# explorer.net
KiCad netlist of a schematic drawn in EAGLE
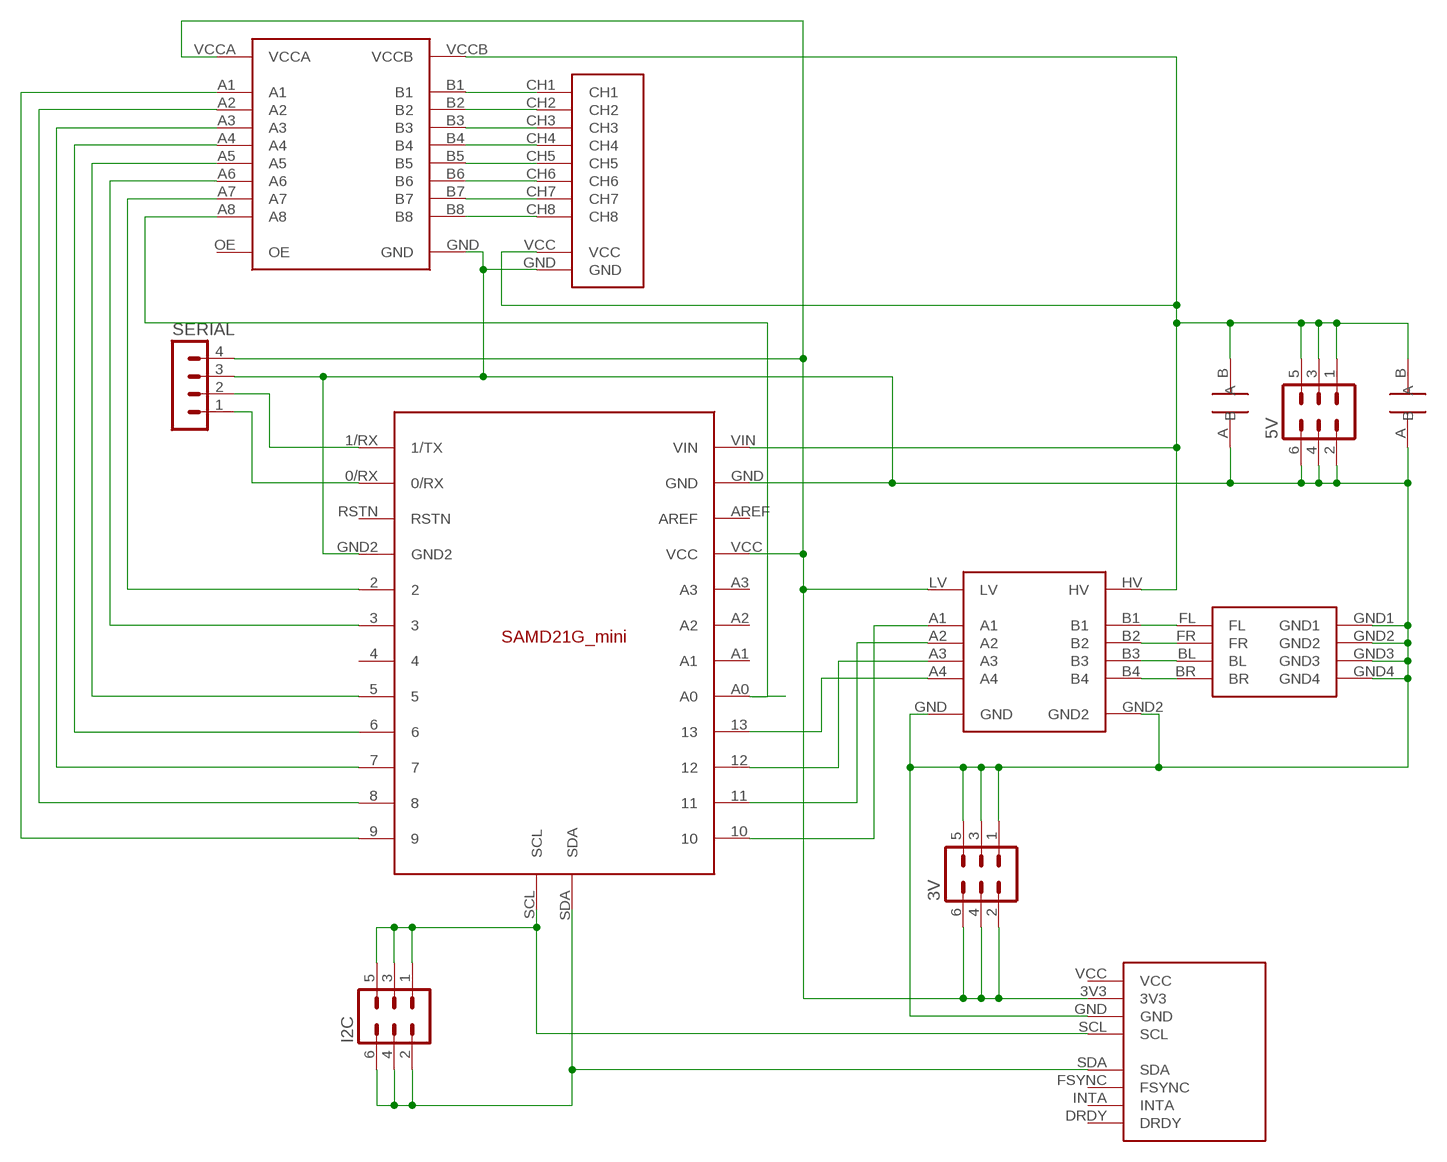
[diagram p0: schematic, sheet 1]

(export (version "E")
  (design (tool "Eeschema 10.0.6"))
  (components
    (comp (ref "3V")
      (value "MA03-2")
      (footprint "eagle-import:MA03-2")
      (libsource (lib "eagle-import") (part "MA03-2"))
    )
    (comp (ref "5V")
      (value "MA03-2")
      (footprint "eagle-import:MA03-2")
      (libsource (lib "eagle-import") (part "MA03-2"))
    )
    (comp (ref "I2C")
      (value "MA03-2")
      (footprint "eagle-import:MA03-2")
      (libsource (lib "eagle-import") (part "MA03-2"))
    )
    (comp (ref "SERIAL")
      (value "MA04-1")
      (footprint "eagle-import:MA04-1")
      (libsource (lib "eagle-import") (part "MA04-1"))
    )
    (comp (ref "U$1")
      (value "MOTOR_HEADER")
      (footprint "eagle-import:MOTOR_HEADER")
      (libsource (lib "eagle-import") (part "MOTOR_HEADER"))
    )
    (comp (ref "U$2")
      (value "CAP")
      (footprint "eagle-import:CAP")
      (libsource (lib "eagle-import") (part "CAP"))
    )
    (comp (ref "U$3")
      (value "SAMD21G_MINI")
      (footprint "eagle-import:SAMD21G-MINI")
      (libsource (lib "eagle-import") (part "SAMD21G_MINI"))
    )
    (comp (ref "U$4")
      (value "LEVELSHIFT_8CH")
      (footprint "eagle-import:LEVELSHIFT_8CH")
      (libsource (lib "eagle-import") (part "LEVELSHIFT_8CH"))
    )
    (comp (ref "U$5")
      (value "LEVELSHIFT_4CH")
      (footprint "eagle-import:LEVELSHIFT_4CH")
      (libsource (lib "eagle-import") (part "LEVELSHIFT_4CH"))
    )
    (comp (ref "U$6")
      (value "RADIO_8CH")
      (footprint "eagle-import:RADIO_8CH")
      (libsource (lib "eagle-import") (part "RADIO_8CH"))
    )
    (comp (ref "U$7")
      (value "CAP")
      (footprint "eagle-import:CAP")
      (libsource (lib "eagle-import") (part "CAP"))
    )
    (comp (ref "U$8")
      (value "GY-86")
      (footprint "eagle-import:GY-86")
      (libsource (lib "eagle-import") (part "GY-86"))
    )
  )
  (nets
    (net (code "1") (name "Net-(3V-Pad1)") (class "Default")
      (node (ref "3V") (pin "1") (pinfunction "1_1") (pintype "passive"))
      (node (ref "3V") (pin "3") (pinfunction "3_3") (pintype "passive"))
      (node (ref "3V") (pin "5") (pinfunction "5_5") (pintype "passive"))
      (node (ref "5V") (pin "2") (pinfunction "2_2") (pintype "passive"))
      (node (ref "5V") (pin "4") (pinfunction "4_4") (pintype "passive"))
      (node (ref "5V") (pin "6") (pinfunction "6_6") (pintype "passive"))
      (node (ref "SERIAL") (pin "3") (pinfunction "3_3") (pintype "passive"))
      (node (ref "U$1") (pin "GND1") (pinfunction "GND1_GND1") (pintype "bidirectional"))
      (node (ref "U$1") (pin "GND2") (pinfunction "GND2_GND2") (pintype "bidirectional"))
      (node (ref "U$1") (pin "GND3") (pinfunction "GND3_GND3") (pintype "bidirectional"))
      (node (ref "U$1") (pin "GND4") (pinfunction "GND4_GND4") (pintype "bidirectional"))
      (node (ref "U$2") (pin "A") (pinfunction "A_A") (pintype "bidirectional"))
      (node (ref "U$3") (pin "GND") (pinfunction "GND_GND") (pintype "bidirectional"))
      (node (ref "U$3") (pin "GND2") (pinfunction "GND2_GND2") (pintype "bidirectional"))
      (node (ref "U$4") (pin "GND") (pinfunction "GND_GND") (pintype "bidirectional"))
      (node (ref "U$5") (pin "GND") (pinfunction "GND_GND") (pintype "bidirectional"))
      (node (ref "U$5") (pin "GND2") (pinfunction "GND2_GND2") (pintype "bidirectional"))
      (node (ref "U$6") (pin "GND") (pinfunction "GND_GND") (pintype "bidirectional"))
      (node (ref "U$7") (pin "A") (pinfunction "A_A") (pintype "bidirectional"))
      (node (ref "U$8") (pin "GND") (pinfunction "GND_GND") (pintype "bidirectional"))
    )
    (net (code "2") (name "Net-(3V-Pad2)") (class "Default")
      (node (ref "3V") (pin "2") (pinfunction "2_2") (pintype "passive"))
      (node (ref "3V") (pin "4") (pinfunction "4_4") (pintype "passive"))
      (node (ref "3V") (pin "6") (pinfunction "6_6") (pintype "passive"))
      (node (ref "SERIAL") (pin "4") (pinfunction "4_4") (pintype "passive"))
      (node (ref "U$3") (pin "VCC") (pinfunction "VCC_VCC") (pintype "bidirectional"))
      (node (ref "U$4") (pin "VCCA") (pinfunction "VCCA_VCCA") (pintype "bidirectional"))
      (node (ref "U$5") (pin "LV") (pinfunction "LV_LV") (pintype "bidirectional"))
      (node (ref "U$8") (pin "3V3") (pinfunction "3V3_3V3") (pintype "bidirectional"))
    )
    (net (code "3") (name "Net-(5V-Pad1)") (class "Default")
      (node (ref "5V") (pin "1") (pinfunction "1_1") (pintype "passive"))
      (node (ref "5V") (pin "3") (pinfunction "3_3") (pintype "passive"))
      (node (ref "5V") (pin "5") (pinfunction "5_5") (pintype "passive"))
      (node (ref "U$2") (pin "B") (pinfunction "B_B") (pintype "bidirectional"))
      (node (ref "U$3") (pin "VIN") (pinfunction "VIN_VIN") (pintype "bidirectional"))
      (node (ref "U$4") (pin "VCCB") (pinfunction "VCCB_VCCB") (pintype "bidirectional"))
      (node (ref "U$5") (pin "HV") (pinfunction "HV_HV") (pintype "bidirectional"))
      (node (ref "U$6") (pin "VCC") (pinfunction "VCC_VCC") (pintype "bidirectional"))
      (node (ref "U$7") (pin "B") (pinfunction "B_B") (pintype "bidirectional"))
    )
    (net (code "4") (name "Net-(I2C-Pad1)") (class "Default")
      (node (ref "I2C") (pin "1") (pinfunction "1_1") (pintype "passive"))
      (node (ref "I2C") (pin "3") (pinfunction "3_3") (pintype "passive"))
      (node (ref "I2C") (pin "5") (pinfunction "5_5") (pintype "passive"))
      (node (ref "U$3") (pin "SCL") (pinfunction "SCL_SCL") (pintype "bidirectional"))
      (node (ref "U$8") (pin "SCL") (pinfunction "SCL_SCL") (pintype "bidirectional"))
    )
    (net (code "5") (name "Net-(I2C-Pad2)") (class "Default")
      (node (ref "I2C") (pin "2") (pinfunction "2_2") (pintype "passive"))
      (node (ref "I2C") (pin "4") (pinfunction "4_4") (pintype "passive"))
      (node (ref "I2C") (pin "6") (pinfunction "6_6") (pintype "passive"))
      (node (ref "U$3") (pin "SDA") (pinfunction "SDA_SDA") (pintype "bidirectional"))
      (node (ref "U$8") (pin "SDA") (pinfunction "SDA_SDA") (pintype "bidirectional"))
    )
    (net (code "6") (name "Net-(SERIAL-Pad1)") (class "Default")
      (node (ref "SERIAL") (pin "1") (pinfunction "1_1") (pintype "passive"))
      (node (ref "U$3") (pin "0/RX") (pinfunction "0/RX_0/RX") (pintype "bidirectional"))
    )
    (net (code "7") (name "Net-(U$1-PadBL)") (class "Default")
      (node (ref "U$1") (pin "BL") (pinfunction "BL_BL") (pintype "bidirectional"))
      (node (ref "U$5") (pin "B3") (pinfunction "B3_B3") (pintype "bidirectional"))
    )
    (net (code "8") (name "Net-(U$1-PadBR)") (class "Default")
      (node (ref "U$1") (pin "BR") (pinfunction "BR_BR") (pintype "bidirectional"))
      (node (ref "U$5") (pin "B4") (pinfunction "B4_B4") (pintype "bidirectional"))
    )
    (net (code "9") (name "Net-(U$1-PadFL)") (class "Default")
      (node (ref "U$1") (pin "FL") (pinfunction "FL_FL") (pintype "bidirectional"))
      (node (ref "U$5") (pin "B1") (pinfunction "B1_B1") (pintype "bidirectional"))
    )
    (net (code "10") (name "Net-(U$1-PadFR)") (class "Default")
      (node (ref "U$1") (pin "FR") (pinfunction "FR_FR") (pintype "bidirectional"))
      (node (ref "U$5") (pin "B2") (pinfunction "B2_B2") (pintype "bidirectional"))
    )
    (net (code "11") (name "Net-(U$3-1{slash}TX)") (class "Default")
      (node (ref "SERIAL") (pin "2") (pinfunction "2_2") (pintype "passive"))
      (node (ref "U$3") (pin "1/RX") (pinfunction "1/TX_1/RX") (pintype "bidirectional"))
    )
    (net (code "12") (name "Net-(U$3-Pad2)") (class "Default")
      (node (ref "U$3") (pin "2") (pinfunction "2_2") (pintype "bidirectional"))
      (node (ref "U$4") (pin "A7") (pinfunction "A7_A7") (pintype "bidirectional"))
    )
    (net (code "13") (name "Net-(U$3-Pad3)") (class "Default")
      (node (ref "U$3") (pin "3") (pinfunction "3_3") (pintype "bidirectional"))
      (node (ref "U$4") (pin "A6") (pinfunction "A6_A6") (pintype "bidirectional"))
    )
    (net (code "14") (name "Net-(U$3-Pad5)") (class "Default")
      (node (ref "U$3") (pin "5") (pinfunction "5_5") (pintype "bidirectional"))
      (node (ref "U$4") (pin "A5") (pinfunction "A5_A5") (pintype "bidirectional"))
    )
    (net (code "15") (name "Net-(U$3-Pad6)") (class "Default")
      (node (ref "U$3") (pin "6") (pinfunction "6_6") (pintype "bidirectional"))
      (node (ref "U$4") (pin "A4") (pinfunction "A4_A4") (pintype "bidirectional"))
    )
    (net (code "16") (name "Net-(U$3-Pad7)") (class "Default")
      (node (ref "U$3") (pin "7") (pinfunction "7_7") (pintype "bidirectional"))
      (node (ref "U$4") (pin "A3") (pinfunction "A3_A3") (pintype "bidirectional"))
    )
    (net (code "17") (name "Net-(U$3-Pad8)") (class "Default")
      (node (ref "U$3") (pin "8") (pinfunction "8_8") (pintype "bidirectional"))
      (node (ref "U$4") (pin "A2") (pinfunction "A2_A2") (pintype "bidirectional"))
    )
    (net (code "18") (name "Net-(U$3-Pad9)") (class "Default")
      (node (ref "U$3") (pin "9") (pinfunction "9_9") (pintype "bidirectional"))
      (node (ref "U$4") (pin "A1") (pinfunction "A1_A1") (pintype "bidirectional"))
    )
    (net (code "19") (name "Net-(U$3-Pad10)") (class "Default")
      (node (ref "U$3") (pin "10") (pinfunction "10_10") (pintype "bidirectional"))
      (node (ref "U$5") (pin "A1") (pinfunction "A1_A1") (pintype "bidirectional"))
    )
    (net (code "20") (name "Net-(U$3-Pad11)") (class "Default")
      (node (ref "U$3") (pin "11") (pinfunction "11_11") (pintype "bidirectional"))
      (node (ref "U$5") (pin "A2") (pinfunction "A2_A2") (pintype "bidirectional"))
    )
    (net (code "21") (name "Net-(U$3-Pad12)") (class "Default")
      (node (ref "U$3") (pin "12") (pinfunction "12_12") (pintype "bidirectional"))
      (node (ref "U$5") (pin "A3") (pinfunction "A3_A3") (pintype "bidirectional"))
    )
    (net (code "22") (name "Net-(U$3-Pad13)") (class "Default")
      (node (ref "U$3") (pin "13") (pinfunction "13_13") (pintype "bidirectional"))
      (node (ref "U$5") (pin "A4") (pinfunction "A4_A4") (pintype "bidirectional"))
    )
    (net (code "23") (name "Net-(U$3-PadA0)") (class "Default")
      (node (ref "U$3") (pin "A0") (pinfunction "A0_A0") (pintype "bidirectional"))
      (node (ref "U$4") (pin "A8") (pinfunction "A8_A8") (pintype "bidirectional"))
    )
    (net (code "24") (name "Net-(U$4-PadB1)") (class "Default")
      (node (ref "U$4") (pin "B1") (pinfunction "B1_B1") (pintype "bidirectional"))
      (node (ref "U$6") (pin "CH1") (pinfunction "CH1_CH1") (pintype "bidirectional"))
    )
    (net (code "25") (name "Net-(U$4-PadB2)") (class "Default")
      (node (ref "U$4") (pin "B2") (pinfunction "B2_B2") (pintype "bidirectional"))
      (node (ref "U$6") (pin "CH2") (pinfunction "CH2_CH2") (pintype "bidirectional"))
    )
    (net (code "26") (name "Net-(U$4-PadB3)") (class "Default")
      (node (ref "U$4") (pin "B3") (pinfunction "B3_B3") (pintype "bidirectional"))
      (node (ref "U$6") (pin "CH3") (pinfunction "CH3_CH3") (pintype "bidirectional"))
    )
    (net (code "27") (name "Net-(U$4-PadB4)") (class "Default")
      (node (ref "U$4") (pin "B4") (pinfunction "B4_B4") (pintype "bidirectional"))
      (node (ref "U$6") (pin "CH4") (pinfunction "CH4_CH4") (pintype "bidirectional"))
    )
    (net (code "28") (name "Net-(U$4-PadB5)") (class "Default")
      (node (ref "U$4") (pin "B5") (pinfunction "B5_B5") (pintype "bidirectional"))
      (node (ref "U$6") (pin "CH5") (pinfunction "CH5_CH5") (pintype "bidirectional"))
    )
    (net (code "29") (name "Net-(U$4-PadB6)") (class "Default")
      (node (ref "U$4") (pin "B6") (pinfunction "B6_B6") (pintype "bidirectional"))
      (node (ref "U$6") (pin "CH6") (pinfunction "CH6_CH6") (pintype "bidirectional"))
    )
    (net (code "30") (name "Net-(U$4-PadB7)") (class "Default")
      (node (ref "U$4") (pin "B7") (pinfunction "B7_B7") (pintype "bidirectional"))
      (node (ref "U$6") (pin "CH7") (pinfunction "CH7_CH7") (pintype "bidirectional"))
    )
    (net (code "31") (name "Net-(U$4-PadB8)") (class "Default")
      (node (ref "U$4") (pin "B8") (pinfunction "B8_B8") (pintype "bidirectional"))
      (node (ref "U$6") (pin "CH8") (pinfunction "CH8_CH8") (pintype "bidirectional"))
    )
    (net (code "32") (name "unconnected-(U$3-Pad4)") (class "Default")
      (node (ref "U$3") (pin "4") (pinfunction "4_4") (pintype "bidirectional"))
    )
    (net (code "33") (name "unconnected-(U$3-PadA1)") (class "Default")
      (node (ref "U$3") (pin "A1") (pinfunction "A1_A1") (pintype "bidirectional"))
    )
    (net (code "34") (name "unconnected-(U$3-PadA2)") (class "Default")
      (node (ref "U$3") (pin "A2") (pinfunction "A2_A2") (pintype "bidirectional"))
    )
    (net (code "35") (name "unconnected-(U$3-PadA3)") (class "Default")
      (node (ref "U$3") (pin "A3") (pinfunction "A3_A3") (pintype "bidirectional"))
    )
    (net (code "36") (name "unconnected-(U$3-PadAREF)") (class "Default")
      (node (ref "U$3") (pin "AREF") (pinfunction "AREF_AREF") (pintype "bidirectional"))
    )
    (net (code "37") (name "unconnected-(U$3-PadRSTN)") (class "Default")
      (node (ref "U$3") (pin "RSTN") (pinfunction "RSTN_RSTN") (pintype "bidirectional"))
    )
    (net (code "38") (name "unconnected-(U$4-PadOE)") (class "Default")
      (node (ref "U$4") (pin "OE") (pinfunction "OE_OE") (pintype "bidirectional"))
    )
    (net (code "39") (name "unconnected-(U$8-PadDRDY)") (class "Default")
      (node (ref "U$8") (pin "DRDY") (pinfunction "DRDY_DRDY") (pintype "bidirectional"))
    )
    (net (code "40") (name "unconnected-(U$8-PadFSYNC)") (class "Default")
      (node (ref "U$8") (pin "FSYNC") (pinfunction "FSYNC_FSYNC") (pintype "bidirectional"))
    )
    (net (code "41") (name "unconnected-(U$8-PadINTA)") (class "Default")
      (node (ref "U$8") (pin "INTA") (pinfunction "INTA_INTA") (pintype "bidirectional"))
    )
    (net (code "42") (name "unconnected-(U$8-PadVCC)") (class "Default")
      (node (ref "U$8") (pin "VCC") (pinfunction "VCC_VCC") (pintype "bidirectional"))
    )
  )
)
